# BL702.net
KiCad netlist of a schematic drawn in Altium Designer
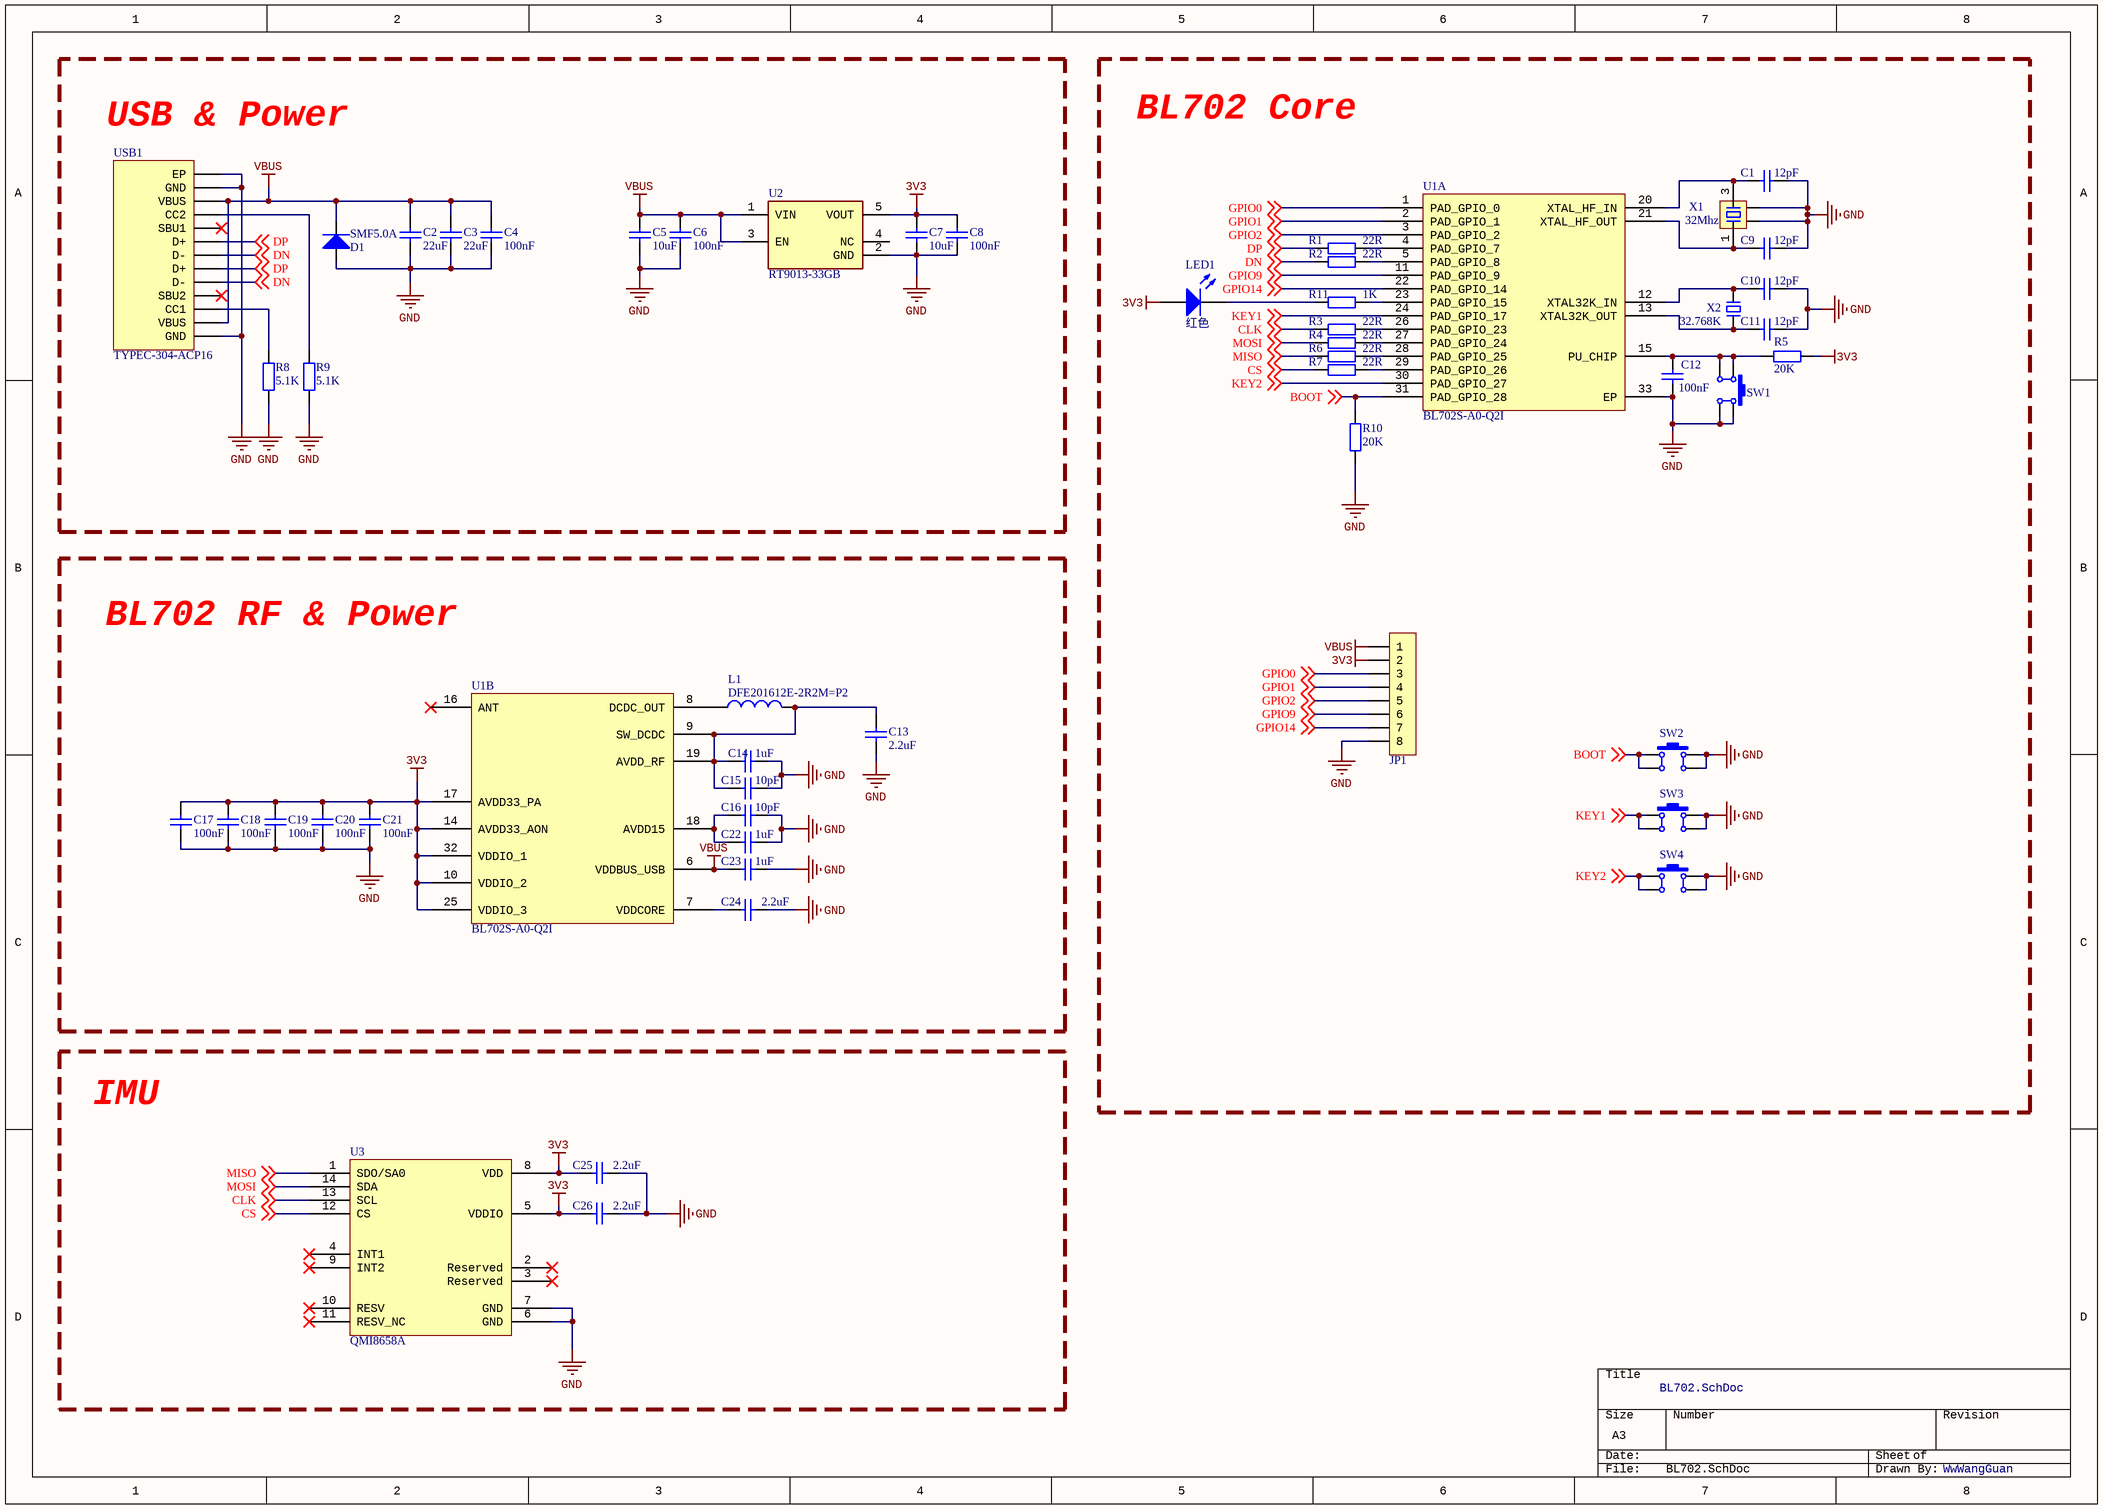
[diagram p0: BL702.SchDoc]

(export (version "E")
  (design (tool "Eeschema 10.0.6"))
  (components
    (comp (ref "C1")
      (value "12pF")
      (footprint "C0402_L")
      (description "贴片电容/MLCC电容")
      (libsource (lib "0.1 - 电阻-电容-电感-保险丝-晶振-晶体-磁珠-电位器-法拉电容-馈通电容") (part "C"))
    )
    (comp (ref "C2")
      (value "22uF")
      (footprint "C0603_L")
      (description "贴片电容/MLCC电容")
      (libsource (lib "0.1 - 电阻-电容-电感-保险丝-晶振-晶体-磁珠-电位器-法拉电容-馈通电容") (part "C"))
    )
    (comp (ref "C3")
      (value "22uF")
      (footprint "C0603_L")
      (description "贴片电容/MLCC电容")
      (libsource (lib "0.1 - 电阻-电容-电感-保险丝-晶振-晶体-磁珠-电位器-法拉电容-馈通电容") (part "C"))
    )
    (comp (ref "C4")
      (value "100nF")
      (footprint "C0603_L")
      (description "贴片电容/MLCC电容")
      (libsource (lib "0.1 - 电阻-电容-电感-保险丝-晶振-晶体-磁珠-电位器-法拉电容-馈通电容") (part "C"))
    )
    (comp (ref "C5")
      (value "10uF")
      (footprint "C0603_L")
      (description "贴片电容/MLCC电容")
      (libsource (lib "0.1 - 电阻-电容-电感-保险丝-晶振-晶体-磁珠-电位器-法拉电容-馈通电容") (part "C"))
    )
    (comp (ref "C6")
      (value "100nF")
      (footprint "C0603_L")
      (description "贴片电容/MLCC电容")
      (libsource (lib "0.1 - 电阻-电容-电感-保险丝-晶振-晶体-磁珠-电位器-法拉电容-馈通电容") (part "C"))
    )
    (comp (ref "C7")
      (value "10uF")
      (footprint "C0603_L")
      (description "贴片电容/MLCC电容")
      (libsource (lib "0.1 - 电阻-电容-电感-保险丝-晶振-晶体-磁珠-电位器-法拉电容-馈通电容") (part "C"))
    )
    (comp (ref "C8")
      (value "100nF")
      (footprint "C0603_L")
      (description "贴片电容/MLCC电容")
      (libsource (lib "0.1 - 电阻-电容-电感-保险丝-晶振-晶体-磁珠-电位器-法拉电容-馈通电容") (part "C"))
    )
    (comp (ref "C9")
      (value "12pF")
      (footprint "C0402_L")
      (description "贴片电容/MLCC电容")
      (libsource (lib "0.1 - 电阻-电容-电感-保险丝-晶振-晶体-磁珠-电位器-法拉电容-馈通电容") (part "C"))
    )
    (comp (ref "C10")
      (value "12pF")
      (footprint "C0402_L")
      (description "贴片电容/MLCC电容")
      (libsource (lib "0.1 - 电阻-电容-电感-保险丝-晶振-晶体-磁珠-电位器-法拉电容-馈通电容") (part "C"))
    )
    (comp (ref "C11")
      (value "12pF")
      (footprint "C0402_L")
      (description "贴片电容/MLCC电容")
      (libsource (lib "0.1 - 电阻-电容-电感-保险丝-晶振-晶体-磁珠-电位器-法拉电容-馈通电容") (part "C"))
    )
    (comp (ref "C12")
      (value "100nF")
      (footprint "C0402_L")
      (description "贴片电容/MLCC电容")
      (libsource (lib "0.1 - 电阻-电容-电感-保险丝-晶振-晶体-磁珠-电位器-法拉电容-馈通电容") (part "C"))
    )
    (comp (ref "C13")
      (value "2.2uF")
      (footprint "C0402_L")
      (description "贴片电容/MLCC电容")
      (libsource (lib "0.1 - 电阻-电容-电感-保险丝-晶振-晶体-磁珠-电位器-法拉电容-馈通电容") (part "C"))
    )
    (comp (ref "C14")
      (value "1uF")
      (footprint "C0402_L")
      (description "贴片电容/MLCC电容")
      (libsource (lib "0.1 - 电阻-电容-电感-保险丝-晶振-晶体-磁珠-电位器-法拉电容-馈通电容") (part "C"))
    )
    (comp (ref "C15")
      (value "10pF")
      (footprint "C0402_L")
      (description "贴片电容/MLCC电容")
      (libsource (lib "0.1 - 电阻-电容-电感-保险丝-晶振-晶体-磁珠-电位器-法拉电容-馈通电容") (part "C"))
    )
    (comp (ref "C16")
      (value "10pF")
      (footprint "C0402_L")
      (description "贴片电容/MLCC电容")
      (libsource (lib "0.1 - 电阻-电容-电感-保险丝-晶振-晶体-磁珠-电位器-法拉电容-馈通电容") (part "C"))
    )
    (comp (ref "C17")
      (value "100nF")
      (footprint "C0402_L")
      (description "贴片电容/MLCC电容")
      (libsource (lib "0.1 - 电阻-电容-电感-保险丝-晶振-晶体-磁珠-电位器-法拉电容-馈通电容") (part "C"))
    )
    (comp (ref "C18")
      (value "100nF")
      (footprint "C0402_L")
      (description "贴片电容/MLCC电容")
      (libsource (lib "0.1 - 电阻-电容-电感-保险丝-晶振-晶体-磁珠-电位器-法拉电容-馈通电容") (part "C"))
    )
    (comp (ref "C19")
      (value "100nF")
      (footprint "C0402_L")
      (description "贴片电容/MLCC电容")
      (libsource (lib "0.1 - 电阻-电容-电感-保险丝-晶振-晶体-磁珠-电位器-法拉电容-馈通电容") (part "C"))
    )
    (comp (ref "C20")
      (value "100nF")
      (footprint "C0402_L")
      (description "贴片电容/MLCC电容")
      (libsource (lib "0.1 - 电阻-电容-电感-保险丝-晶振-晶体-磁珠-电位器-法拉电容-馈通电容") (part "C"))
    )
    (comp (ref "C21")
      (value "100nF")
      (footprint "C0402_L")
      (description "贴片电容/MLCC电容")
      (libsource (lib "0.1 - 电阻-电容-电感-保险丝-晶振-晶体-磁珠-电位器-法拉电容-馈通电容") (part "C"))
    )
    (comp (ref "C22")
      (value "1uF")
      (footprint "C0402_L")
      (description "贴片电容/MLCC电容")
      (libsource (lib "0.1 - 电阻-电容-电感-保险丝-晶振-晶体-磁珠-电位器-法拉电容-馈通电容") (part "C"))
    )
    (comp (ref "C23")
      (value "1uF")
      (footprint "C0402_L")
      (description "贴片电容/MLCC电容")
      (libsource (lib "0.1 - 电阻-电容-电感-保险丝-晶振-晶体-磁珠-电位器-法拉电容-馈通电容") (part "C"))
    )
    (comp (ref "C24")
      (value "2.2uF")
      (footprint "C0402_L")
      (description "贴片电容/MLCC电容")
      (libsource (lib "0.1 - 电阻-电容-电感-保险丝-晶振-晶体-磁珠-电位器-法拉电容-馈通电容") (part "C"))
    )
    (comp (ref "C25")
      (value "2.2uF")
      (footprint "C0402_L")
      (description "贴片电容/MLCC电容")
      (libsource (lib "0.1 - 电阻-电容-电感-保险丝-晶振-晶体-磁珠-电位器-法拉电容-馈通电容") (part "C"))
    )
    (comp (ref "C26")
      (value "2.2uF")
      (footprint "C0402_L")
      (description "贴片电容/MLCC电容")
      (libsource (lib "0.1 - 电阻-电容-电感-保险丝-晶振-晶体-磁珠-电位器-法拉电容-馈通电容") (part "C"))
    )
    (comp (ref "D1")
      (value "SMF5.0A")
      (footprint "SOD-123")
      (description "TVS通用")
      (libsource (lib "0.2 - 二极管-TVS-ESD-整流桥-放电管") (part "TVS"))
    )
    (comp (ref "JP1")
      (value "HDR-1X8")
      (footprint "HDR2.54-LI-8P")
      (description "8P接插件")
      (libsource (lib "5.5 - 2.54mm连接器(KF2EDGK_XH2.54_2.54排针排母)") (part "Header 8"))
    )
    (comp (ref "L1")
      (value "DFE201612E-2R2M=P2")
      (footprint "FP-DFE201612C-IPC_B")
      (description "Inductor Power Shielded Wirewound 2.2uH 20% 1MHz Metal 1.8A 0.116Ohm DCR 0806 T/R")
      (libsource (lib "Riva") (part "IND-2"))
    )
    (comp (ref "LED1")
      (value "红色")
      (footprint "LED0603_R")
      (description "贴片LED")
      (libsource (lib "0.3 - LED发光二极管-IR二极管_接收管-光耦") (part "LED"))
    )
    (comp (ref "R1")
      (value "22R")
      (footprint "R0402_L")
      (description "贴片电阻")
      (libsource (lib "0.1 - 电阻-电容-电感-保险丝-晶振-晶体-磁珠-电位器-法拉电容-馈通电容") (part "R"))
    )
    (comp (ref "R2")
      (value "22R")
      (footprint "R0402_L")
      (description "贴片电阻")
      (libsource (lib "0.1 - 电阻-电容-电感-保险丝-晶振-晶体-磁珠-电位器-法拉电容-馈通电容") (part "R"))
    )
    (comp (ref "R3")
      (value "22R")
      (footprint "R0402_L")
      (description "贴片电阻")
      (libsource (lib "0.1 - 电阻-电容-电感-保险丝-晶振-晶体-磁珠-电位器-法拉电容-馈通电容") (part "R"))
    )
    (comp (ref "R4")
      (value "22R")
      (footprint "R0402_L")
      (description "贴片电阻")
      (libsource (lib "0.1 - 电阻-电容-电感-保险丝-晶振-晶体-磁珠-电位器-法拉电容-馈通电容") (part "R"))
    )
    (comp (ref "R5")
      (value "20K")
      (footprint "R0402_L")
      (description "贴片电阻")
      (libsource (lib "0.1 - 电阻-电容-电感-保险丝-晶振-晶体-磁珠-电位器-法拉电容-馈通电容") (part "R"))
    )
    (comp (ref "R6")
      (value "22R")
      (footprint "R0402_L")
      (description "贴片电阻")
      (libsource (lib "0.1 - 电阻-电容-电感-保险丝-晶振-晶体-磁珠-电位器-法拉电容-馈通电容") (part "R"))
    )
    (comp (ref "R7")
      (value "22R")
      (footprint "R0402_L")
      (description "贴片电阻")
      (libsource (lib "0.1 - 电阻-电容-电感-保险丝-晶振-晶体-磁珠-电位器-法拉电容-馈通电容") (part "R"))
    )
    (comp (ref "R8")
      (value "5.1K")
      (footprint "R0402_L")
      (description "贴片电阻")
      (libsource (lib "0.1 - 电阻-电容-电感-保险丝-晶振-晶体-磁珠-电位器-法拉电容-馈通电容") (part "R"))
    )
    (comp (ref "R9")
      (value "5.1K")
      (footprint "R0402_L")
      (description "贴片电阻")
      (libsource (lib "0.1 - 电阻-电容-电感-保险丝-晶振-晶体-磁珠-电位器-法拉电容-馈通电容") (part "R"))
    )
    (comp (ref "R10")
      (value "20K")
      (footprint "R0402_L")
      (description "贴片电阻")
      (libsource (lib "0.1 - 电阻-电容-电感-保险丝-晶振-晶体-磁珠-电位器-法拉电容-馈通电容") (part "R"))
    )
    (comp (ref "R11")
      (value "1K")
      (footprint "R0402_L")
      (description "贴片电阻")
      (libsource (lib "0.1 - 电阻-电容-电感-保险丝-晶振-晶体-磁珠-电位器-法拉电容-馈通电容") (part "R"))
    )
    (comp (ref "SW1")
      (value "3*4*2.5")
      (footprint "SW-SMD-4.2x3.2_4P")
      (description "贴片4脚轻触开关")
      (libsource (lib "0.5 - 按键_开关_蜂鸣器_电池_测试点_Mark点_铜柱") (part "SW SMD-3*4*2.5"))
    )
    (comp (ref "SW2")
      (value "3*4*2.5")
      (footprint "SW-SMD-4.2x3.2_4P")
      (description "贴片4脚轻触开关")
      (libsource (lib "0.5 - 按键_开关_蜂鸣器_电池_测试点_Mark点_铜柱") (part "SW SMD-3*4*2.5"))
    )
    (comp (ref "SW3")
      (value "3*4*2.5")
      (footprint "SW-SMD-4.2x3.2_4P")
      (description "贴片4脚轻触开关")
      (libsource (lib "0.5 - 按键_开关_蜂鸣器_电池_测试点_Mark点_铜柱") (part "SW SMD-3*4*2.5"))
    )
    (comp (ref "SW4")
      (value "3*4*2.5")
      (footprint "SW-SMD-4.2x3.2_4P")
      (description "贴片4脚轻触开关")
      (libsource (lib "0.5 - 按键_开关_蜂鸣器_电池_测试点_Mark点_铜柱") (part "SW SMD-3*4*2.5"))
    )
    (comp (ref "U1")
      (value "BL702S-A0-Q2I")
      (footprint "QFN40P400X400X80_HS-33N")
      (description "BL702")
      (libsource (lib "Riva") (part "BL702S-A0-Q2I"))
    )
    (comp (ref "U2")
      (value "RT9013-33GB")
      (footprint "SamacSys:SOT94P279X130-5N")
      (description "Power Supply")
      (fields (field (name "MOUSER PART NUMBER") "835-RT9013-33GB"))
      (libsource (lib "SamacSys") (part "RT9013-33GB"))
    )
    (comp (ref "U3")
      (value "QMI8658A")
      (footprint "PQFN50P300X250X86-14M")
      (libsource (lib "Riva") (part "QMI8658A"))
    )
    (comp (ref "USB1")
      (value "TYPEC-304-ACP16")
      (footprint "TYPEC-304-ACP16-Footprint-1")
      (description "3A 1 Horizontal attachment 16P Female -40℃~+85℃ Gold Copper Type-C SMD USB Connectors ROHS")
      (libsource (lib "Riva") (part "TYPEC-16P"))
    )
    (comp (ref "X1")
      (value "32Mhz")
      (footprint "XTAL-3225-4P")
      (description "4脚无源晶振(谐振器）")
      (libsource (lib "0.1 - 电阻-电容-电感-保险丝-晶振-晶体-磁珠-电位器-法拉电容-馈通电容") (part "XTAL-4P"))
    )
    (comp (ref "X2")
      (value "32.768K")
      (footprint "XTAL-3215-2P")
      (description "2脚无源晶振(谐振器）")
      (libsource (lib "0.1 - 电阻-电容-电感-保险丝-晶振-晶体-磁珠-电位器-法拉电容-馈通电容") (part "XTAL-2P"))
    )
  )
  (nets
    (net (code "1") (name "3V3") (class "Default")
      (node (ref "C17") (pin "1") (pinfunction "1_1") (pintype "passive"))
      (node (ref "C18") (pin "1") (pinfunction "1_1") (pintype "passive"))
      (node (ref "C19") (pin "1") (pinfunction "1_1") (pintype "passive"))
      (node (ref "C20") (pin "1") (pinfunction "1_1") (pintype "passive"))
      (node (ref "C21") (pin "1") (pinfunction "1_1") (pintype "passive"))
      (node (ref "C25") (pin "2") (pinfunction "2_2") (pintype "passive"))
      (node (ref "C26") (pin "2") (pinfunction "2_2") (pintype "passive"))
      (node (ref "C7") (pin "2") (pinfunction "2_2") (pintype "passive"))
      (node (ref "C8") (pin "2") (pinfunction "2_2") (pintype "passive"))
      (node (ref "JP1") (pin "2") (pinfunction "2_2") (pintype "passive"))
      (node (ref "LED1") (pin "1") (pinfunction "A_1") (pintype "passive"))
      (node (ref "R5") (pin "1") (pinfunction "1_1") (pintype "passive"))
      (node (ref "U1") (pin "10") (pinfunction "VDDIO_2_10") (pintype "passive"))
      (node (ref "U1") (pin "14") (pinfunction "AVDD33_AON_14") (pintype "passive"))
      (node (ref "U1") (pin "17") (pinfunction "AVDD33_PA_17") (pintype "passive"))
      (node (ref "U1") (pin "25") (pinfunction "VDDIO_3_25") (pintype "passive"))
      (node (ref "U1") (pin "32") (pinfunction "VDDIO_1_32") (pintype "passive"))
      (node (ref "U2") (pin "5") (pinfunction "VOUT_5") (pintype "passive"))
      (node (ref "U3") (pin "5") (pinfunction "VDDIO_5") (pintype "passive"))
      (node (ref "U3") (pin "8") (pinfunction "VDD_8") (pintype "passive"))
    )
    (net (code "2") (name "BOOT") (class "Default")
      (node (ref "R10") (pin "1") (pinfunction "1_1") (pintype "passive"))
      (node (ref "SW2") (pin "2") (pinfunction "2_2") (pintype "passive"))
      (node (ref "SW2") (pin "3") (pinfunction "3_3") (pintype "passive"))
      (node (ref "U1") (pin "31") (pinfunction "PAD_GPIO_28_31") (pintype "passive"))
    )
    (net (code "3") (name "CLK") (class "Default")
      (node (ref "R3") (pin "2") (pinfunction "2_2") (pintype "passive"))
      (node (ref "U3") (pin "13") (pinfunction "SCL_13") (pintype "passive"))
    )
    (net (code "4") (name "CS") (class "Default")
      (node (ref "R7") (pin "2") (pinfunction "2_2") (pintype "passive"))
      (node (ref "U3") (pin "12") (pinfunction "CS_12") (pintype "passive"))
    )
    (net (code "5") (name "DN") (class "Default")
      (node (ref "R2") (pin "2") (pinfunction "2_2") (pintype "passive"))
      (node (ref "USB1") (pin "A7") (pinfunction "D-_A7") (pintype "passive"))
      (node (ref "USB1") (pin "B7") (pinfunction "D-_B7") (pintype "passive"))
    )
    (net (code "6") (name "DP") (class "Default")
      (node (ref "R1") (pin "2") (pinfunction "2_2") (pintype "passive"))
      (node (ref "USB1") (pin "A6") (pinfunction "D+_A6") (pintype "passive"))
      (node (ref "USB1") (pin "B6") (pinfunction "D+_B6") (pintype "passive"))
    )
    (net (code "7") (name "GND") (class "Default")
      (node (ref "C1") (pin "1") (pinfunction "1_1") (pintype "passive"))
      (node (ref "C10") (pin "1") (pinfunction "1_1") (pintype "passive"))
      (node (ref "C11") (pin "1") (pinfunction "1_1") (pintype "passive"))
      (node (ref "C12") (pin "1") (pinfunction "1_1") (pintype "passive"))
      (node (ref "C13") (pin "1") (pinfunction "1_1") (pintype "passive"))
      (node (ref "C14") (pin "1") (pinfunction "1_1") (pintype "passive"))
      (node (ref "C15") (pin "2") (pinfunction "2_2") (pintype "passive"))
      (node (ref "C16") (pin "2") (pinfunction "2_2") (pintype "passive"))
      (node (ref "C17") (pin "2") (pinfunction "2_2") (pintype "passive"))
      (node (ref "C18") (pin "2") (pinfunction "2_2") (pintype "passive"))
      (node (ref "C19") (pin "2") (pinfunction "2_2") (pintype "passive"))
      (node (ref "C2") (pin "1") (pinfunction "1_1") (pintype "passive"))
      (node (ref "C20") (pin "2") (pinfunction "2_2") (pintype "passive"))
      (node (ref "C21") (pin "2") (pinfunction "2_2") (pintype "passive"))
      (node (ref "C22") (pin "1") (pinfunction "1_1") (pintype "passive"))
      (node (ref "C23") (pin "2") (pinfunction "2_2") (pintype "passive"))
      (node (ref "C24") (pin "1") (pinfunction "1_1") (pintype "passive"))
      (node (ref "C25") (pin "1") (pinfunction "1_1") (pintype "passive"))
      (node (ref "C26") (pin "1") (pinfunction "1_1") (pintype "passive"))
      (node (ref "C3") (pin "1") (pinfunction "1_1") (pintype "passive"))
      (node (ref "C4") (pin "1") (pinfunction "1_1") (pintype "passive"))
      (node (ref "C5") (pin "1") (pinfunction "1_1") (pintype "passive"))
      (node (ref "C6") (pin "1") (pinfunction "1_1") (pintype "passive"))
      (node (ref "C7") (pin "1") (pinfunction "1_1") (pintype "passive"))
      (node (ref "C8") (pin "1") (pinfunction "1_1") (pintype "passive"))
      (node (ref "C9") (pin "1") (pinfunction "1_1") (pintype "passive"))
      (node (ref "D1") (pin "1") (pinfunction "A_1") (pintype "passive"))
      (node (ref "JP1") (pin "8") (pinfunction "8_8") (pintype "passive"))
      (node (ref "R10") (pin "2") (pinfunction "2_2") (pintype "passive"))
      (node (ref "R8") (pin "1") (pinfunction "1_1") (pintype "passive"))
      (node (ref "R9") (pin "1") (pinfunction "1_1") (pintype "passive"))
      (node (ref "SW1") (pin "2") (pinfunction "2_2") (pintype "passive"))
      (node (ref "SW1") (pin "3") (pinfunction "3_3") (pintype "passive"))
      (node (ref "SW2") (pin "1") (pinfunction "1_1") (pintype "passive"))
      (node (ref "SW2") (pin "4") (pinfunction "4_4") (pintype "passive"))
      (node (ref "SW3") (pin "1") (pinfunction "1_1") (pintype "passive"))
      (node (ref "SW3") (pin "4") (pinfunction "4_4") (pintype "passive"))
      (node (ref "SW4") (pin "1") (pinfunction "1_1") (pintype "passive"))
      (node (ref "SW4") (pin "4") (pinfunction "4_4") (pintype "passive"))
      (node (ref "U1") (pin "33") (pinfunction "EP_33") (pintype "passive"))
      (node (ref "U2") (pin "2") (pinfunction "GND_2") (pintype "passive"))
      (node (ref "U3") (pin "6") (pinfunction "GND_6") (pintype "passive"))
      (node (ref "U3") (pin "7") (pinfunction "GND_7") (pintype "passive"))
      (node (ref "USB1") (pin "A1B12") (pinfunction "GND_A1B12") (pintype "passive"))
      (node (ref "USB1") (pin "B1A12") (pinfunction "GND_B1A12") (pintype "passive"))
      (node (ref "USB1") (pin "EP") (pinfunction "EP_EP") (pintype "passive"))
      (node (ref "X1") (pin "2") (pinfunction "2_2") (pintype "passive"))
      (node (ref "X1") (pin "4") (pinfunction "4_4") (pintype "passive"))
    )
    (net (code "8") (name "GPIO0") (class "Default")
      (node (ref "JP1") (pin "3") (pinfunction "3_3") (pintype "passive"))
      (node (ref "U1") (pin "1") (pinfunction "PAD_GPIO_0_1") (pintype "passive"))
    )
    (net (code "9") (name "GPIO1") (class "Default")
      (node (ref "JP1") (pin "4") (pinfunction "4_4") (pintype "passive"))
      (node (ref "U1") (pin "2") (pinfunction "PAD_GPIO_1_2") (pintype "passive"))
    )
    (net (code "10") (name "GPIO2") (class "Default")
      (node (ref "JP1") (pin "5") (pinfunction "5_5") (pintype "passive"))
      (node (ref "U1") (pin "3") (pinfunction "PAD_GPIO_2_3") (pintype "passive"))
    )
    (net (code "11") (name "GPIO9") (class "Default")
      (node (ref "JP1") (pin "6") (pinfunction "6_6") (pintype "passive"))
      (node (ref "U1") (pin "11") (pinfunction "PAD_GPIO_9_11") (pintype "passive"))
    )
    (net (code "12") (name "GPIO14") (class "Default")
      (node (ref "JP1") (pin "7") (pinfunction "7_7") (pintype "passive"))
      (node (ref "U1") (pin "22") (pinfunction "PAD_GPIO_14_22") (pintype "passive"))
    )
    (net (code "13") (name "KEY1") (class "Default")
      (node (ref "SW3") (pin "2") (pinfunction "2_2") (pintype "passive"))
      (node (ref "SW3") (pin "3") (pinfunction "3_3") (pintype "passive"))
      (node (ref "U1") (pin "24") (pinfunction "PAD_GPIO_17_24") (pintype "passive"))
    )
    (net (code "14") (name "KEY2") (class "Default")
      (node (ref "SW4") (pin "2") (pinfunction "2_2") (pintype "passive"))
      (node (ref "SW4") (pin "3") (pinfunction "3_3") (pintype "passive"))
      (node (ref "U1") (pin "30") (pinfunction "PAD_GPIO_27_30") (pintype "passive"))
    )
    (net (code "15") (name "MISO") (class "Default")
      (node (ref "R6") (pin "2") (pinfunction "2_2") (pintype "passive"))
      (node (ref "U3") (pin "1") (pinfunction "SDO/SA0_1") (pintype "passive"))
    )
    (net (code "16") (name "MOSI") (class "Default")
      (node (ref "R4") (pin "2") (pinfunction "2_2") (pintype "passive"))
      (node (ref "U3") (pin "14") (pinfunction "SDA_14") (pintype "passive"))
    )
    (net (code "17") (name "Net-(LED1-K)") (class "Default")
      (node (ref "LED1") (pin "2") (pinfunction "K_2") (pintype "passive"))
      (node (ref "R11") (pin "2") (pinfunction "2_2") (pintype "passive"))
    )
    (net (code "18") (name "Net-(U1A-PAD_GPIO_7)") (class "Default")
      (node (ref "R1") (pin "1") (pinfunction "1_1") (pintype "passive"))
      (node (ref "U1") (pin "4") (pinfunction "PAD_GPIO_7_4") (pintype "passive"))
    )
    (net (code "19") (name "Net-(U1A-PAD_GPIO_8)") (class "Default")
      (node (ref "R2") (pin "1") (pinfunction "1_1") (pintype "passive"))
      (node (ref "U1") (pin "5") (pinfunction "PAD_GPIO_8_5") (pintype "passive"))
    )
    (net (code "20") (name "Net-(U1A-PAD_GPIO_15)") (class "Default")
      (node (ref "R11") (pin "1") (pinfunction "1_1") (pintype "passive"))
      (node (ref "U1") (pin "23") (pinfunction "PAD_GPIO_15_23") (pintype "passive"))
    )
    (net (code "21") (name "Net-(U1A-PAD_GPIO_23)") (class "Default")
      (node (ref "R3") (pin "1") (pinfunction "1_1") (pintype "passive"))
      (node (ref "U1") (pin "26") (pinfunction "PAD_GPIO_23_26") (pintype "passive"))
    )
    (net (code "22") (name "Net-(U1A-PAD_GPIO_24)") (class "Default")
      (node (ref "R4") (pin "1") (pinfunction "1_1") (pintype "passive"))
      (node (ref "U1") (pin "27") (pinfunction "PAD_GPIO_24_27") (pintype "passive"))
    )
    (net (code "23") (name "Net-(U1A-PAD_GPIO_25)") (class "Default")
      (node (ref "R6") (pin "1") (pinfunction "1_1") (pintype "passive"))
      (node (ref "U1") (pin "28") (pinfunction "PAD_GPIO_25_28") (pintype "passive"))
    )
    (net (code "24") (name "Net-(U1A-PAD_GPIO_26)") (class "Default")
      (node (ref "R7") (pin "1") (pinfunction "1_1") (pintype "passive"))
      (node (ref "U1") (pin "29") (pinfunction "PAD_GPIO_26_29") (pintype "passive"))
    )
    (net (code "25") (name "Net-(U1A-PU_CHIP)") (class "Default")
      (node (ref "C12") (pin "2") (pinfunction "2_2") (pintype "passive"))
      (node (ref "R5") (pin "2") (pinfunction "2_2") (pintype "passive"))
      (node (ref "SW1") (pin "1") (pinfunction "1_1") (pintype "passive"))
      (node (ref "SW1") (pin "4") (pinfunction "4_4") (pintype "passive"))
      (node (ref "U1") (pin "15") (pinfunction "PU_CHIP_15") (pintype "passive"))
    )
    (net (code "26") (name "Net-(U1A-XTAL32K_IN)") (class "Default")
      (node (ref "C10") (pin "2") (pinfunction "2_2") (pintype "passive"))
      (node (ref "U1") (pin "12") (pinfunction "XTAL32K_IN_12") (pintype "passive"))
      (node (ref "X2") (pin "2") (pinfunction "2_2") (pintype "passive"))
    )
    (net (code "27") (name "Net-(U1A-XTAL32K_OUT)") (class "Default")
      (node (ref "C11") (pin "2") (pinfunction "2_2") (pintype "passive"))
      (node (ref "U1") (pin "13") (pinfunction "XTAL32K_OUT_13") (pintype "passive"))
      (node (ref "X2") (pin "1") (pinfunction "1_1") (pintype "passive"))
    )
    (net (code "28") (name "Net-(U1A-XTAL_HF_IN)") (class "Default")
      (node (ref "C1") (pin "2") (pinfunction "2_2") (pintype "passive"))
      (node (ref "U1") (pin "20") (pinfunction "XTAL_HF_IN_20") (pintype "passive"))
      (node (ref "X1") (pin "3") (pinfunction "3_3") (pintype "passive"))
    )
    (net (code "29") (name "Net-(U1A-XTAL_HF_OUT)") (class "Default")
      (node (ref "C9") (pin "2") (pinfunction "2_2") (pintype "passive"))
      (node (ref "U1") (pin "21") (pinfunction "XTAL_HF_OUT_21") (pintype "passive"))
      (node (ref "X1") (pin "1") (pinfunction "1_1") (pintype "passive"))
    )
    (net (code "30") (name "Net-(U1B-AVDD15)") (class "Default")
      (node (ref "C16") (pin "1") (pinfunction "1_1") (pintype "passive"))
      (node (ref "C22") (pin "2") (pinfunction "2_2") (pintype "passive"))
      (node (ref "U1") (pin "18") (pinfunction "AVDD15_18") (pintype "passive"))
    )
    (net (code "31") (name "Net-(U1B-AVDD_RF)") (class "Default")
      (node (ref "C13") (pin "2") (pinfunction "2_2") (pintype "passive"))
      (node (ref "C14") (pin "2") (pinfunction "2_2") (pintype "passive"))
      (node (ref "C15") (pin "1") (pinfunction "1_1") (pintype "passive"))
      (node (ref "L1") (pin "2") (pinfunction "2_2") (pintype "passive"))
      (node (ref "U1") (pin "19") (pinfunction "AVDD_RF_19") (pintype "passive"))
      (node (ref "U1") (pin "9") (pinfunction "SW_DCDC_9") (pintype "passive"))
    )
    (net (code "32") (name "Net-(U1B-DCDC_OUT)") (class "Default")
      (node (ref "L1") (pin "1") (pinfunction "1_1") (pintype "passive"))
      (node (ref "U1") (pin "8") (pinfunction "DCDC_OUT_8") (pintype "passive"))
    )
    (net (code "33") (name "Net-(U1B-VDDCORE)") (class "Default")
      (node (ref "C24") (pin "2") (pinfunction "2_2") (pintype "passive"))
      (node (ref "U1") (pin "7") (pinfunction "VDDCORE_7") (pintype "passive"))
    )
    (net (code "34") (name "Net-(USB1-CC1)") (class "Default")
      (node (ref "R8") (pin "2") (pinfunction "2_2") (pintype "passive"))
      (node (ref "USB1") (pin "A5") (pinfunction "CC1_A5") (pintype "passive"))
    )
    (net (code "35") (name "Net-(USB1-CC2)") (class "Default")
      (node (ref "R9") (pin "2") (pinfunction "2_2") (pintype "passive"))
      (node (ref "USB1") (pin "B5") (pinfunction "CC2_B5") (pintype "passive"))
    )
    (net (code "36") (name "VBUS") (class "Default")
      (node (ref "C2") (pin "2") (pinfunction "2_2") (pintype "passive"))
      (node (ref "C23") (pin "1") (pinfunction "1_1") (pintype "passive"))
      (node (ref "C3") (pin "2") (pinfunction "2_2") (pintype "passive"))
      (node (ref "C4") (pin "2") (pinfunction "2_2") (pintype "passive"))
      (node (ref "C5") (pin "2") (pinfunction "2_2") (pintype "passive"))
      (node (ref "C6") (pin "2") (pinfunction "2_2") (pintype "passive"))
      (node (ref "D1") (pin "2") (pinfunction "K_2") (pintype "passive"))
      (node (ref "JP1") (pin "1") (pinfunction "1_1") (pintype "passive"))
      (node (ref "U1") (pin "6") (pinfunction "VDDBUS_USB_6") (pintype "passive"))
      (node (ref "U2") (pin "1") (pinfunction "VIN_1") (pintype "passive"))
      (node (ref "U2") (pin "3") (pinfunction "EN_3") (pintype "passive"))
      (node (ref "USB1") (pin "A4B9") (pinfunction "VBUS_A4B9") (pintype "passive"))
      (node (ref "USB1") (pin "B4A9") (pinfunction "VBUS_B4A9") (pintype "passive"))
    )
    (net (code "37") (name "unconnected-(U1B-ANT-Pad16)") (class "Default")
      (node (ref "U1") (pin "16") (pinfunction "ANT_16") (pintype "passive+no_connect"))
    )
    (net (code "38") (name "unconnected-(U2-NC-Pad4)") (class "Default")
      (node (ref "U2") (pin "4") (pinfunction "NC_4") (pintype "passive"))
    )
    (net (code "39") (name "unconnected-(U3-INT1-Pad4)") (class "Default")
      (node (ref "U3") (pin "4") (pinfunction "INT1_4") (pintype "passive+no_connect"))
    )
    (net (code "40") (name "unconnected-(U3-INT2-Pad9)") (class "Default")
      (node (ref "U3") (pin "9") (pinfunction "INT2_9") (pintype "passive+no_connect"))
    )
    (net (code "41") (name "unconnected-(U3-RESV-Pad10)") (class "Default")
      (node (ref "U3") (pin "10") (pinfunction "RESV_10") (pintype "passive+no_connect"))
    )
    (net (code "42") (name "unconnected-(U3-RESV_NC-Pad11)") (class "Default")
      (node (ref "U3") (pin "11") (pinfunction "RESV_NC_11") (pintype "passive+no_connect"))
    )
    (net (code "43") (name "unconnected-(U3-Reserved-Pad2)") (class "Default")
      (node (ref "U3") (pin "2") (pinfunction "Reserved_2") (pintype "passive+no_connect"))
    )
    (net (code "44") (name "unconnected-(U3-Reserved-Pad3)") (class "Default")
      (node (ref "U3") (pin "3") (pinfunction "Reserved_3") (pintype "passive+no_connect"))
    )
    (net (code "45") (name "unconnected-(USB1-SBU1-PadA8)") (class "Default")
      (node (ref "USB1") (pin "A8") (pinfunction "SBU1_A8") (pintype "passive+no_connect"))
    )
    (net (code "46") (name "unconnected-(USB1-SBU2-PadB8)") (class "Default")
      (node (ref "USB1") (pin "B8") (pinfunction "SBU2_B8") (pintype "passive+no_connect"))
    )
  )
)
